# bmp280_i2c.net
KiCad netlist of a schematic drawn in Altium Designer
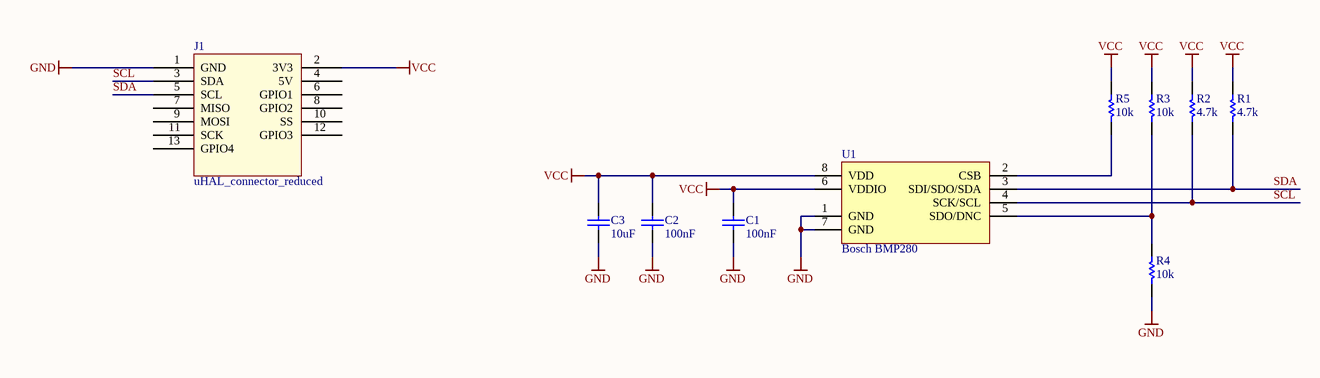
[diagram p0: bmp280_i2c.SchDoc]

(export (version "E")
  (design (tool "Eeschema 10.0.6"))
  (components
    (comp (ref "C1")
      (value "Murata GCM188R71H104KA57D")
      (footprint "CAPC1608X90X35ML10T15")
      (description "CAP CER 0.1UF 50V 10% X7R 0603")
      (fields (field (name "CAPACITANCE") "100nF"))
      (libsource (lib "CommunityVault") (part "CMP-119667-3"))
    )
    (comp (ref "C2")
      (value "Murata GCM188R71H104KA57D")
      (footprint "CAPC1608X90X35ML10T15")
      (description "CAP CER 0.1UF 50V 10% X7R 0603")
      (fields (field (name "CAPACITANCE") "100nF"))
      (libsource (lib "CommunityVault") (part "CMP-119667-3"))
    )
    (comp (ref "C3")
      (value "Murata GCM188R71H104KA57D")
      (footprint "CAPC1608X90X35ML10T15")
      (description "CAP CER 0.1UF 50V 10% X7R 0603")
      (fields (field (name "CAPACITANCE") "10uF"))
      (libsource (lib "CommunityVault") (part "CMP-119667-3"))
    )
    (comp (ref "J1")
      (value "uHAL_connector_reduced")
      (footprint "PCB-45ncoppm4oopozvqifsq-1")
      (description "connector for uHAL with reduced pin number")
      (libsource (lib "CommunityVault") (part "CMP-2q23h2cwhjlfm8s6r7i8-1"))
    )
    (comp (ref "R1")
      (value "4.7k")
      (footprint "RESC1608X05N")
      (description "RCA Series 0603 0.1 W 0 O Jumper Surface Mount Thick Film Chip Resistor")
      (fields (field (name "MANUFACTURER PART NUMBER") "RCA06030000ZSEA"))
      (libsource (lib "CommunityVault") (part "SYM-31acf99032f6ee6b-1"))
    )
    (comp (ref "R2")
      (value "4.7k")
      (footprint "RESC1608X05N")
      (description "RCA Series 0603 0.1 W 0 O Jumper Surface Mount Thick Film Chip Resistor")
      (fields (field (name "MANUFACTURER PART NUMBER") "RCA06030000ZSEA"))
      (libsource (lib "CommunityVault") (part "SYM-31acf99032f6ee6b-1"))
    )
    (comp (ref "R3")
      (value "10k")
      (footprint "RESC1608X05N")
      (description "RCA Series 0603 0.1 W 0 O Jumper Surface Mount Thick Film Chip Resistor")
      (fields (field (name "MANUFACTURER PART NUMBER") "RCA06030000ZSEA"))
      (libsource (lib "CommunityVault") (part "SYM-31acf99032f6ee6b-1"))
    )
    (comp (ref "R4")
      (value "10k")
      (footprint "RESC1608X05N")
      (description "RCA Series 0603 0.1 W 0 O Jumper Surface Mount Thick Film Chip Resistor")
      (fields (field (name "MANUFACTURER PART NUMBER") "RCA06030000ZSEA"))
      (libsource (lib "CommunityVault") (part "SYM-31acf99032f6ee6b-1"))
    )
    (comp (ref "R5")
      (value "10k")
      (footprint "RESC1608X05N")
      (description "RCA Series 0603 0.1 W 0 O Jumper Surface Mount Thick Film Chip Resistor")
      (fields (field (name "MANUFACTURER PART NUMBER") "RCA06030000ZSEA"))
      (libsource (lib "CommunityVault") (part "SYM-31acf99032f6ee6b-1"))
    )
    (comp (ref "U1")
      (value "Bosch BMP280")
      (footprint "PCB-7ktgzhb423iat7xn8psi-1")
      (description "P-Sensor SPI I2C SMD")
      (fields (field (name "MANUFACTURER PART NUMBER") "BMP280"))
      (libsource (lib "CommunityVault") (part "SYM-f1e0397949ec2e27-1"))
    )
  )
  (nets
    (net (code "1") (name "/SCL") (class "Default")
      (node (ref "J1") (pin "3") (pinfunction "SDA_3") (pintype "passive"))
      (node (ref "R2") (pin "1") (pinfunction "1_1") (pintype "passive"))
      (node (ref "U1") (pin "4") (pinfunction "SCK/SCL_4") (pintype "passive"))
    )
    (net (code "2") (name "/SDA") (class "Default")
      (node (ref "J1") (pin "5") (pinfunction "SCL_5") (pintype "passive"))
      (node (ref "R1") (pin "1") (pinfunction "1_1") (pintype "passive"))
      (node (ref "U1") (pin "3") (pinfunction "SDI/SDO/SDA_3") (pintype "passive"))
    )
    (net (code "3") (name "GND") (class "Default")
      (node (ref "C1") (pin "2") (pinfunction "2_2") (pintype "passive"))
      (node (ref "C2") (pin "2") (pinfunction "2_2") (pintype "passive"))
      (node (ref "C3") (pin "2") (pinfunction "2_2") (pintype "passive"))
      (node (ref "J1") (pin "1") (pinfunction "GND_1") (pintype "passive"))
      (node (ref "R4") (pin "1") (pinfunction "1_1") (pintype "passive"))
      (node (ref "U1") (pin "1") (pinfunction "GND_1") (pintype "power_in"))
      (node (ref "U1") (pin "7") (pinfunction "GND_7") (pintype "power_in"))
    )
    (net (code "4") (name "Net-(U1-CSB)") (class "Default")
      (node (ref "R5") (pin "1") (pinfunction "1_1") (pintype "passive"))
      (node (ref "U1") (pin "2") (pinfunction "CSB_2") (pintype "passive"))
    )
    (net (code "5") (name "Net-(U1-SDO{slash}DNC)") (class "Default")
      (node (ref "R3") (pin "1") (pinfunction "1_1") (pintype "passive"))
      (node (ref "R4") (pin "2") (pinfunction "2_2") (pintype "passive"))
      (node (ref "U1") (pin "5") (pinfunction "SDO/DNC_5") (pintype "passive"))
    )
    (net (code "6") (name "VCC") (class "Default")
      (node (ref "C1") (pin "1") (pinfunction "1_1") (pintype "passive"))
      (node (ref "C2") (pin "1") (pinfunction "1_1") (pintype "passive"))
      (node (ref "C3") (pin "1") (pinfunction "1_1") (pintype "passive"))
      (node (ref "J1") (pin "2") (pinfunction "3V3_2") (pintype "passive"))
      (node (ref "R1") (pin "2") (pinfunction "2_2") (pintype "passive"))
      (node (ref "R2") (pin "2") (pinfunction "2_2") (pintype "passive"))
      (node (ref "R3") (pin "2") (pinfunction "2_2") (pintype "passive"))
      (node (ref "R5") (pin "2") (pinfunction "2_2") (pintype "passive"))
      (node (ref "U1") (pin "6") (pinfunction "VDDIO_6") (pintype "power_in"))
      (node (ref "U1") (pin "8") (pinfunction "VDD_8") (pintype "power_in"))
    )
    (net (code "7") (name "unconnected-(J1-5V-Pad4)") (class "Default")
      (node (ref "J1") (pin "4") (pinfunction "5V_4") (pintype "passive"))
    )
    (net (code "8") (name "unconnected-(J1-GPIO1-Pad6)") (class "Default")
      (node (ref "J1") (pin "6") (pinfunction "GPIO1_6") (pintype "passive"))
    )
    (net (code "9") (name "unconnected-(J1-GPIO2-Pad8)") (class "Default")
      (node (ref "J1") (pin "8") (pinfunction "GPIO2_8") (pintype "passive"))
    )
    (net (code "10") (name "unconnected-(J1-GPIO3-Pad12)") (class "Default")
      (node (ref "J1") (pin "12") (pinfunction "GPIO3_12") (pintype "passive"))
    )
    (net (code "11") (name "unconnected-(J1-GPIO4-Pad13)") (class "Default")
      (node (ref "J1") (pin "13") (pinfunction "GPIO4_13") (pintype "passive"))
    )
    (net (code "12") (name "unconnected-(J1-MISO-Pad7)") (class "Default")
      (node (ref "J1") (pin "7") (pinfunction "MISO_7") (pintype "passive"))
    )
    (net (code "13") (name "unconnected-(J1-MOSI-Pad9)") (class "Default")
      (node (ref "J1") (pin "9") (pinfunction "MOSI_9") (pintype "passive"))
    )
    (net (code "14") (name "unconnected-(J1-SCK-Pad11)") (class "Default")
      (node (ref "J1") (pin "11") (pinfunction "SCK_11") (pintype "passive"))
    )
    (net (code "15") (name "unconnected-(J1-SS-Pad10)") (class "Default")
      (node (ref "J1") (pin "10") (pinfunction "SS_10") (pintype "passive"))
    )
  )
)
